# Schematic.net
KiCad netlist of a schematic drawn in EasyEDA
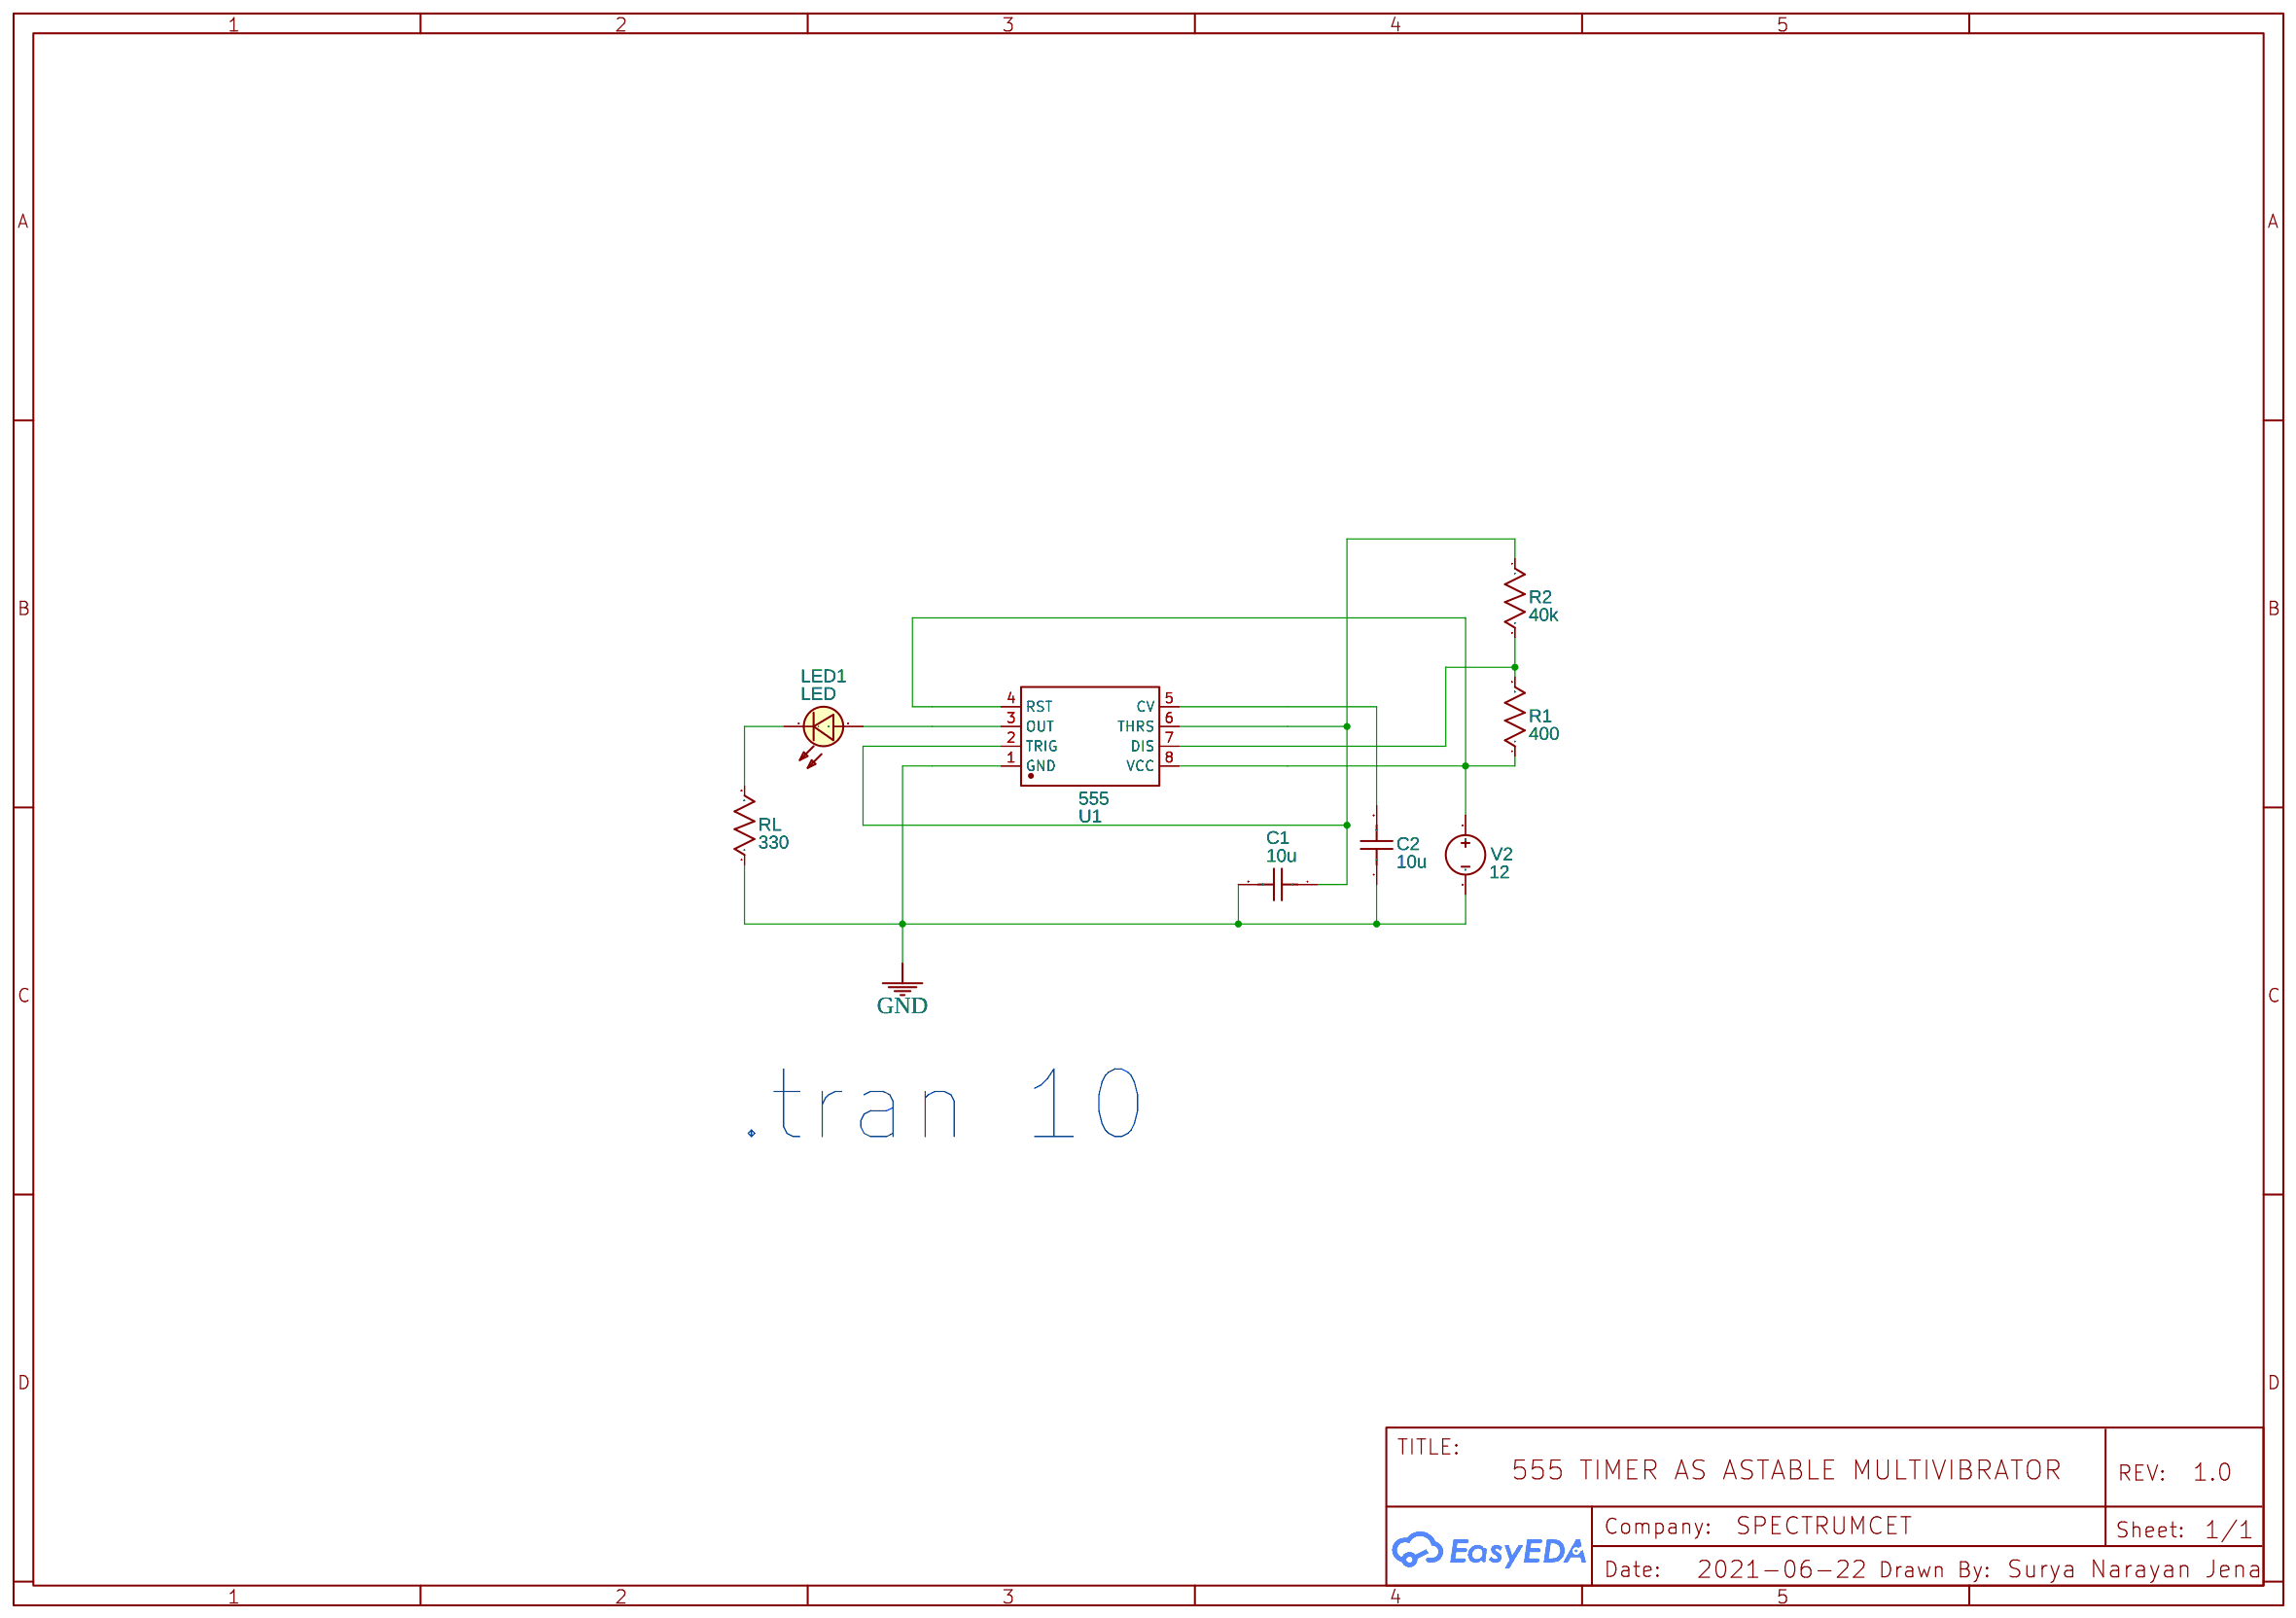
[diagram p0: schematic sheet]

(export (version "E")
  (design (tool "Eeschema 10.0.6"))
  (components
    (comp (ref "C1") (value "10u") (libsource (lib "") (part "C_0603_US_1")))
    (comp (ref "C2") (value "10u") (libsource (lib "") (part "C_0603_US")))
    (comp (ref "LED1") (value "LED") (libsource (lib "") (part "LED")))
    (comp (ref "R1") (value "400") (libsource (lib "") (part "R_0603_US_2")))
    (comp (ref "R2") (value "40k") (libsource (lib "") (part "R_0603_US")))
    (comp (ref "RL") (value "330") (libsource (lib "") (part "R_0603_US_1")))
    (comp (ref "U1") (value "555") (libsource (lib "") (part "555_BJT_EE")))
    (comp (ref "V2") (value "12") (libsource (lib "") (part "VDC")))
  )
  (nets
    (net (code "1") (name "GND") (class "Default")
      (node (ref "C1") (pin "2") (pinfunction "2_2") (pintype "unspecified"))
      (node (ref "C2") (pin "1") (pinfunction "1_1") (pintype "unspecified"))
      (node (ref "RL") (pin "1") (pinfunction "1_1") (pintype "unspecified"))
      (node (ref "U1") (pin "1") (pinfunction "GND_1") (pintype "unspecified"))
      (node (ref "V2") (pin "2") (pinfunction "2_2") (pintype "unspecified"))
    )
    (net (code "2") (name "Net-(LED1-+)") (class "Default")
      (node (ref "LED1") (pin "1") (pinfunction "+_1") (pintype "unspecified"))
      (node (ref "U1") (pin "3") (pinfunction "OUT_3") (pintype "unspecified"))
    )
    (net (code "3") (name "Net-(LED1--)") (class "Default")
      (node (ref "LED1") (pin "2") (pinfunction "-_2") (pintype "unspecified"))
      (node (ref "RL") (pin "2") (pinfunction "2_2") (pintype "unspecified"))
    )
    (net (code "4") (name "Net-(U1-CV)") (class "Default")
      (node (ref "C2") (pin "2") (pinfunction "2_2") (pintype "unspecified"))
      (node (ref "U1") (pin "5") (pinfunction "CV_5") (pintype "unspecified"))
    )
    (net (code "5") (name "Net-(U1-DIS)") (class "Default")
      (node (ref "R1") (pin "2") (pinfunction "2_2") (pintype "unspecified"))
      (node (ref "R2") (pin "2") (pinfunction "2_2") (pintype "unspecified"))
      (node (ref "U1") (pin "7") (pinfunction "DIS_7") (pintype "unspecified"))
    )
    (net (code "6") (name "Net-(U1-RST)") (class "Default")
      (node (ref "R1") (pin "1") (pinfunction "1_1") (pintype "unspecified"))
      (node (ref "U1") (pin "4") (pinfunction "RST_4") (pintype "unspecified"))
      (node (ref "U1") (pin "8") (pinfunction "VCC_8") (pintype "unspecified"))
      (node (ref "V2") (pin "1") (pinfunction "1_1") (pintype "unspecified"))
    )
    (net (code "7") (name "Net-(U1-THRS)") (class "Default")
      (node (ref "C1") (pin "1") (pinfunction "1_1") (pintype "unspecified"))
      (node (ref "R2") (pin "1") (pinfunction "1_1") (pintype "unspecified"))
      (node (ref "U1") (pin "2") (pinfunction "TRIG_2") (pintype "unspecified"))
      (node (ref "U1") (pin "6") (pinfunction "THRS_6") (pintype "unspecified"))
    )
  )
)
